# MRF49XA_Breakout.net
KiCad netlist of a schematic drawn in EAGLE
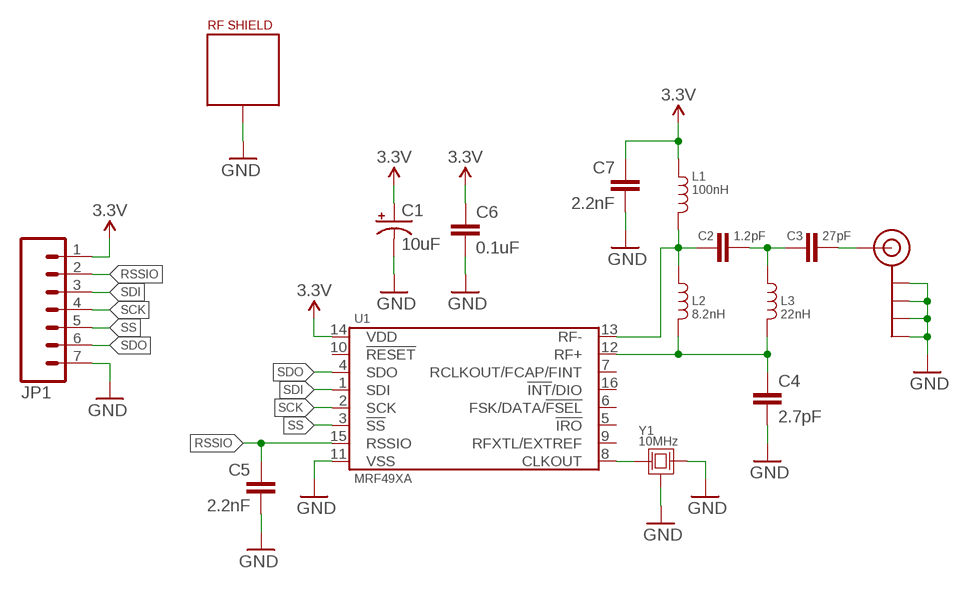
[diagram p0: schematic, sheet 1]

(export (version "E")
  (design (tool "Eeschema 10.0.6"))
  (components
    (comp (ref "C1")
      (value "10uF")
      (footprint "eagle-import:0805-CAP_POL")
      (libsource (lib "eagle-import") (part "CAP_POL0805"))
    )
    (comp (ref "C2")
      (value "1.2pF")
      (footprint "eagle-import:0805")
      (libsource (lib "eagle-import") (part "CAP0805"))
    )
    (comp (ref "C3")
      (value "27pF")
      (footprint "eagle-import:0805")
      (libsource (lib "eagle-import") (part "CAP0805"))
    )
    (comp (ref "C4")
      (value "2.7pF")
      (footprint "eagle-import:0805")
      (libsource (lib "eagle-import") (part "CAP0805"))
    )
    (comp (ref "C5")
      (value "2.2nF")
      (footprint "eagle-import:0805")
      (libsource (lib "eagle-import") (part "CAP0805"))
    )
    (comp (ref "C6")
      (value "0.1uF")
      (footprint "eagle-import:0805")
      (libsource (lib "eagle-import") (part "CAP0805"))
    )
    (comp (ref "C7")
      (value "2.2nF")
      (footprint "eagle-import:0805")
      (libsource (lib "eagle-import") (part "CAP0805"))
    )
    (comp (ref "J$1")
      (value "SMA_EDGE")
      (footprint "eagle-import:SMA-EDGE")
      (libsource (lib "eagle-import") (part "SMA_EDGE"))
    )
    (comp (ref "JP1")
      (value "M07")
      (footprint "eagle-import:1X07")
      (libsource (lib "eagle-import") (part "M07"))
    )
    (comp (ref "L1")
      (value "100nH")
      (footprint "eagle-import:0805")
      (libsource (lib "eagle-import") (part "INDUCTOR-0805"))
    )
    (comp (ref "L2")
      (value "8.2nH")
      (footprint "eagle-import:0805")
      (libsource (lib "eagle-import") (part "INDUCTOR-0805"))
    )
    (comp (ref "L3")
      (value "22nH")
      (footprint "eagle-import:0805")
      (libsource (lib "eagle-import") (part "INDUCTOR-0805"))
    )
    (comp (ref "U$1")
      (value "RF-SHIELD")
      (footprint "eagle-import:RF_SHIELD-.65X.65")
      (libsource (lib "eagle-import") (part "RF-SHIELD"))
    )
    (comp (ref "U1")
      (value "MRF49XA")
      (footprint "eagle-import:TSSOP-16")
      (libsource (lib "eagle-import") (part "MRF49XA"))
    )
    (comp (ref "Y1")
      (value "10MHz")
      (footprint "eagle-import:FA-238")
      (libsource (lib "eagle-import") (part "CRYSTAL-3.2X2.5"))
    )
  )
  (nets
    (net (code "1") (name "3.3V") (class "Default")
      (node (ref "C1") (pin "A") (pinfunction "+_A") (pintype "passive"))
      (node (ref "C6") (pin "1") (pinfunction "1_1") (pintype "passive"))
      (node (ref "C7") (pin "1") (pinfunction "1_1") (pintype "passive"))
      (node (ref "JP1") (pin "1") (pinfunction "1_1") (pintype "passive"))
      (node (ref "L1") (pin "1") (pinfunction "P$1_1") (pintype "bidirectional"))
      (node (ref "U1") (pin "14") (pinfunction "VDD_14") (pintype "bidirectional"))
    )
    (net (code "2") (name "GND") (class "Default")
      (node (ref "C1") (pin "C") (pinfunction "-_C") (pintype "passive"))
      (node (ref "C4") (pin "2") (pinfunction "2_2") (pintype "passive"))
      (node (ref "C5") (pin "2") (pinfunction "2_2") (pintype "passive"))
      (node (ref "C6") (pin "2") (pinfunction "2_2") (pintype "passive"))
      (node (ref "C7") (pin "2") (pinfunction "2_2") (pintype "passive"))
      (node (ref "J$1") (pin "GND@0") (pinfunction "GND_GND@0") (pintype "bidirectional"))
      (node (ref "J$1") (pin "GND@1") (pinfunction "GND_GND@1") (pintype "bidirectional"))
      (node (ref "J$1") (pin "GND@2") (pinfunction "GND_GND@2") (pintype "bidirectional"))
      (node (ref "J$1") (pin "GND@3") (pinfunction "GND_GND@3") (pintype "bidirectional"))
      (node (ref "JP1") (pin "7") (pinfunction "7_7") (pintype "passive"))
      (node (ref "U$1") (pin "P$1") (pinfunction "P$1_P$1") (pintype "bidirectional"))
      (node (ref "U$1") (pin "P$10") (pinfunction "P$1_P$10") (pintype "bidirectional"))
      (node (ref "U$1") (pin "P$11") (pinfunction "P$1_P$11") (pintype "bidirectional"))
      (node (ref "U$1") (pin "P$12") (pinfunction "P$1_P$12") (pintype "bidirectional"))
      (node (ref "U$1") (pin "P$2") (pinfunction "P$1_P$2") (pintype "bidirectional"))
      (node (ref "U$1") (pin "P$3") (pinfunction "P$1_P$3") (pintype "bidirectional"))
      (node (ref "U$1") (pin "P$4") (pinfunction "P$1_P$4") (pintype "bidirectional"))
      (node (ref "U$1") (pin "P$5") (pinfunction "P$1_P$5") (pintype "bidirectional"))
      (node (ref "U$1") (pin "P$6") (pinfunction "P$1_P$6") (pintype "bidirectional"))
      (node (ref "U$1") (pin "P$7") (pinfunction "P$1_P$7") (pintype "bidirectional"))
      (node (ref "U$1") (pin "P$8") (pinfunction "P$1_P$8") (pintype "bidirectional"))
      (node (ref "U$1") (pin "P$9") (pinfunction "P$1_P$9") (pintype "bidirectional"))
      (node (ref "U1") (pin "11") (pinfunction "VSS_11") (pintype "bidirectional"))
      (node (ref "Y1") (pin "2") (pinfunction "GND_2") (pintype "bidirectional"))
      (node (ref "Y1") (pin "3") (pinfunction "2_3") (pintype "bidirectional"))
      (node (ref "Y1") (pin "4") (pinfunction "GND_4") (pintype "bidirectional"))
    )
    (net (code "3") (name "Net-(J$1-SIGNAL)") (class "Default")
      (node (ref "C3") (pin "2") (pinfunction "2_2") (pintype "passive"))
      (node (ref "J$1") (pin "SIG") (pinfunction "SIGNAL_SIG") (pintype "bidirectional"))
    )
    (net (code "4") (name "Net-(L1-P$2)") (class "Default")
      (node (ref "C2") (pin "1") (pinfunction "1_1") (pintype "passive"))
      (node (ref "L1") (pin "2") (pinfunction "P$2_2") (pintype "bidirectional"))
      (node (ref "L2") (pin "1") (pinfunction "P$1_1") (pintype "bidirectional"))
      (node (ref "U1") (pin "13") (pinfunction "RF-_13") (pintype "bidirectional"))
    )
    (net (code "5") (name "Net-(L2-P$2)") (class "Default")
      (node (ref "C4") (pin "1") (pinfunction "1_1") (pintype "passive"))
      (node (ref "L2") (pin "2") (pinfunction "P$2_2") (pintype "bidirectional"))
      (node (ref "L3") (pin "2") (pinfunction "P$2_2") (pintype "bidirectional"))
      (node (ref "U1") (pin "12") (pinfunction "RF+_12") (pintype "bidirectional"))
    )
    (net (code "6") (name "Net-(L3-P$1)") (class "Default")
      (node (ref "C2") (pin "2") (pinfunction "2_2") (pintype "passive"))
      (node (ref "C3") (pin "1") (pinfunction "1_1") (pintype "passive"))
      (node (ref "L3") (pin "1") (pinfunction "P$1_1") (pintype "bidirectional"))
    )
    (net (code "7") (name "Net-(U1-CLKOUT)") (class "Default")
      (node (ref "U1") (pin "8") (pinfunction "CLKOUT_8") (pintype "bidirectional"))
      (node (ref "Y1") (pin "1") (pinfunction "1_1") (pintype "bidirectional"))
    )
    (net (code "8") (name "RSSIO") (class "Default")
      (node (ref "C5") (pin "1") (pinfunction "1_1") (pintype "passive"))
      (node (ref "JP1") (pin "2") (pinfunction "2_2") (pintype "passive"))
      (node (ref "U1") (pin "15") (pinfunction "RSSIO_15") (pintype "bidirectional"))
    )
    (net (code "9") (name "SCK") (class "Default")
      (node (ref "JP1") (pin "4") (pinfunction "4_4") (pintype "passive"))
      (node (ref "U1") (pin "2") (pinfunction "SCK_2") (pintype "bidirectional"))
    )
    (net (code "10") (name "SDI") (class "Default")
      (node (ref "JP1") (pin "3") (pinfunction "3_3") (pintype "passive"))
      (node (ref "U1") (pin "1") (pinfunction "SDI_1") (pintype "bidirectional"))
    )
    (net (code "11") (name "SDO") (class "Default")
      (node (ref "JP1") (pin "6") (pinfunction "6_6") (pintype "passive"))
      (node (ref "U1") (pin "4") (pinfunction "SDO_4") (pintype "bidirectional"))
    )
    (net (code "12") (name "SS") (class "Default")
      (node (ref "JP1") (pin "5") (pinfunction "5_5") (pintype "passive"))
      (node (ref "U1") (pin "3") (pinfunction "~{SS}_3") (pintype "bidirectional"))
    )
    (net (code "13") (name "unconnected-(U1-FSK{slash}DATA{slash}~{FSEL}-Pad6)") (class "Default")
      (node (ref "U1") (pin "6") (pinfunction "FSK/DATA/~{FSEL}_6") (pintype "bidirectional"))
    )
    (net (code "14") (name "unconnected-(U1-RCLKOUT{slash}FCAP{slash}FINT-Pad7)") (class "Default")
      (node (ref "U1") (pin "7") (pinfunction "RCLKOUT/FCAP/FINT_7") (pintype "bidirectional"))
    )
    (net (code "15") (name "unconnected-(U1-RFXTL{slash}EXTREF-Pad9)") (class "Default")
      (node (ref "U1") (pin "9") (pinfunction "RFXTL/EXTREF_9") (pintype "bidirectional"))
    )
    (net (code "16") (name "unconnected-(U1-~{INT}{slash}DIO-Pad16)") (class "Default")
      (node (ref "U1") (pin "16") (pinfunction "~{INT}/DIO_16") (pintype "bidirectional"))
    )
    (net (code "17") (name "unconnected-(U1-~{IRO}-Pad5)") (class "Default")
      (node (ref "U1") (pin "5") (pinfunction "~{IRO}_5") (pintype "bidirectional"))
    )
    (net (code "18") (name "unconnected-(U1-~{RESET}-Pad10)") (class "Default")
      (node (ref "U1") (pin "10") (pinfunction "~{RESET}_10") (pintype "bidirectional"))
    )
  )
)
